# harp_analog_input_v1_0.net
KiCad netlist of a schematic drawn in EAGLE
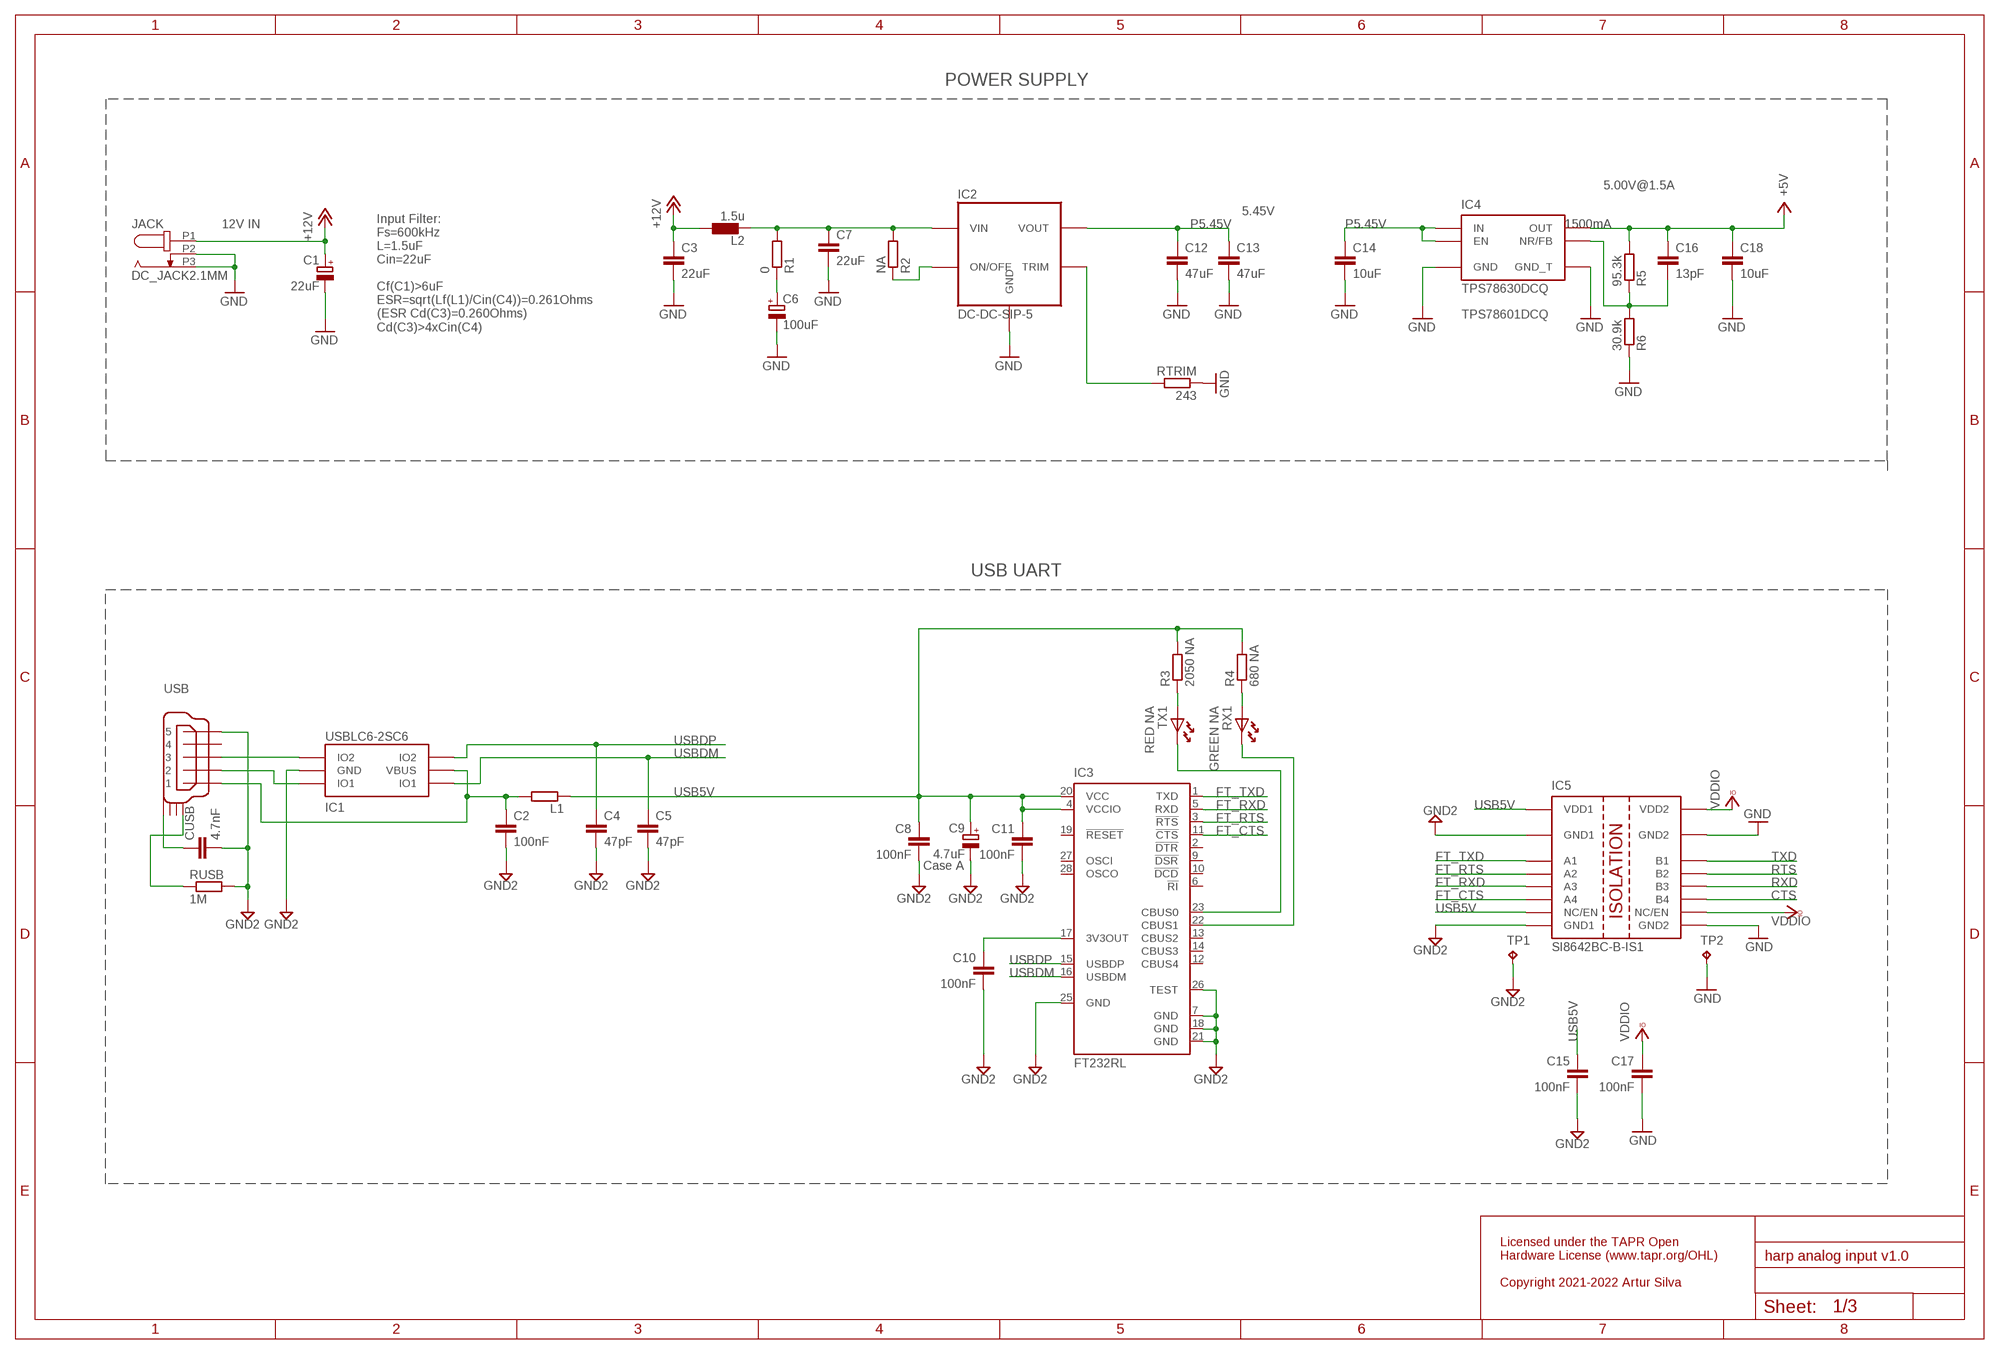
[diagram p0: schematic, sheet 1]
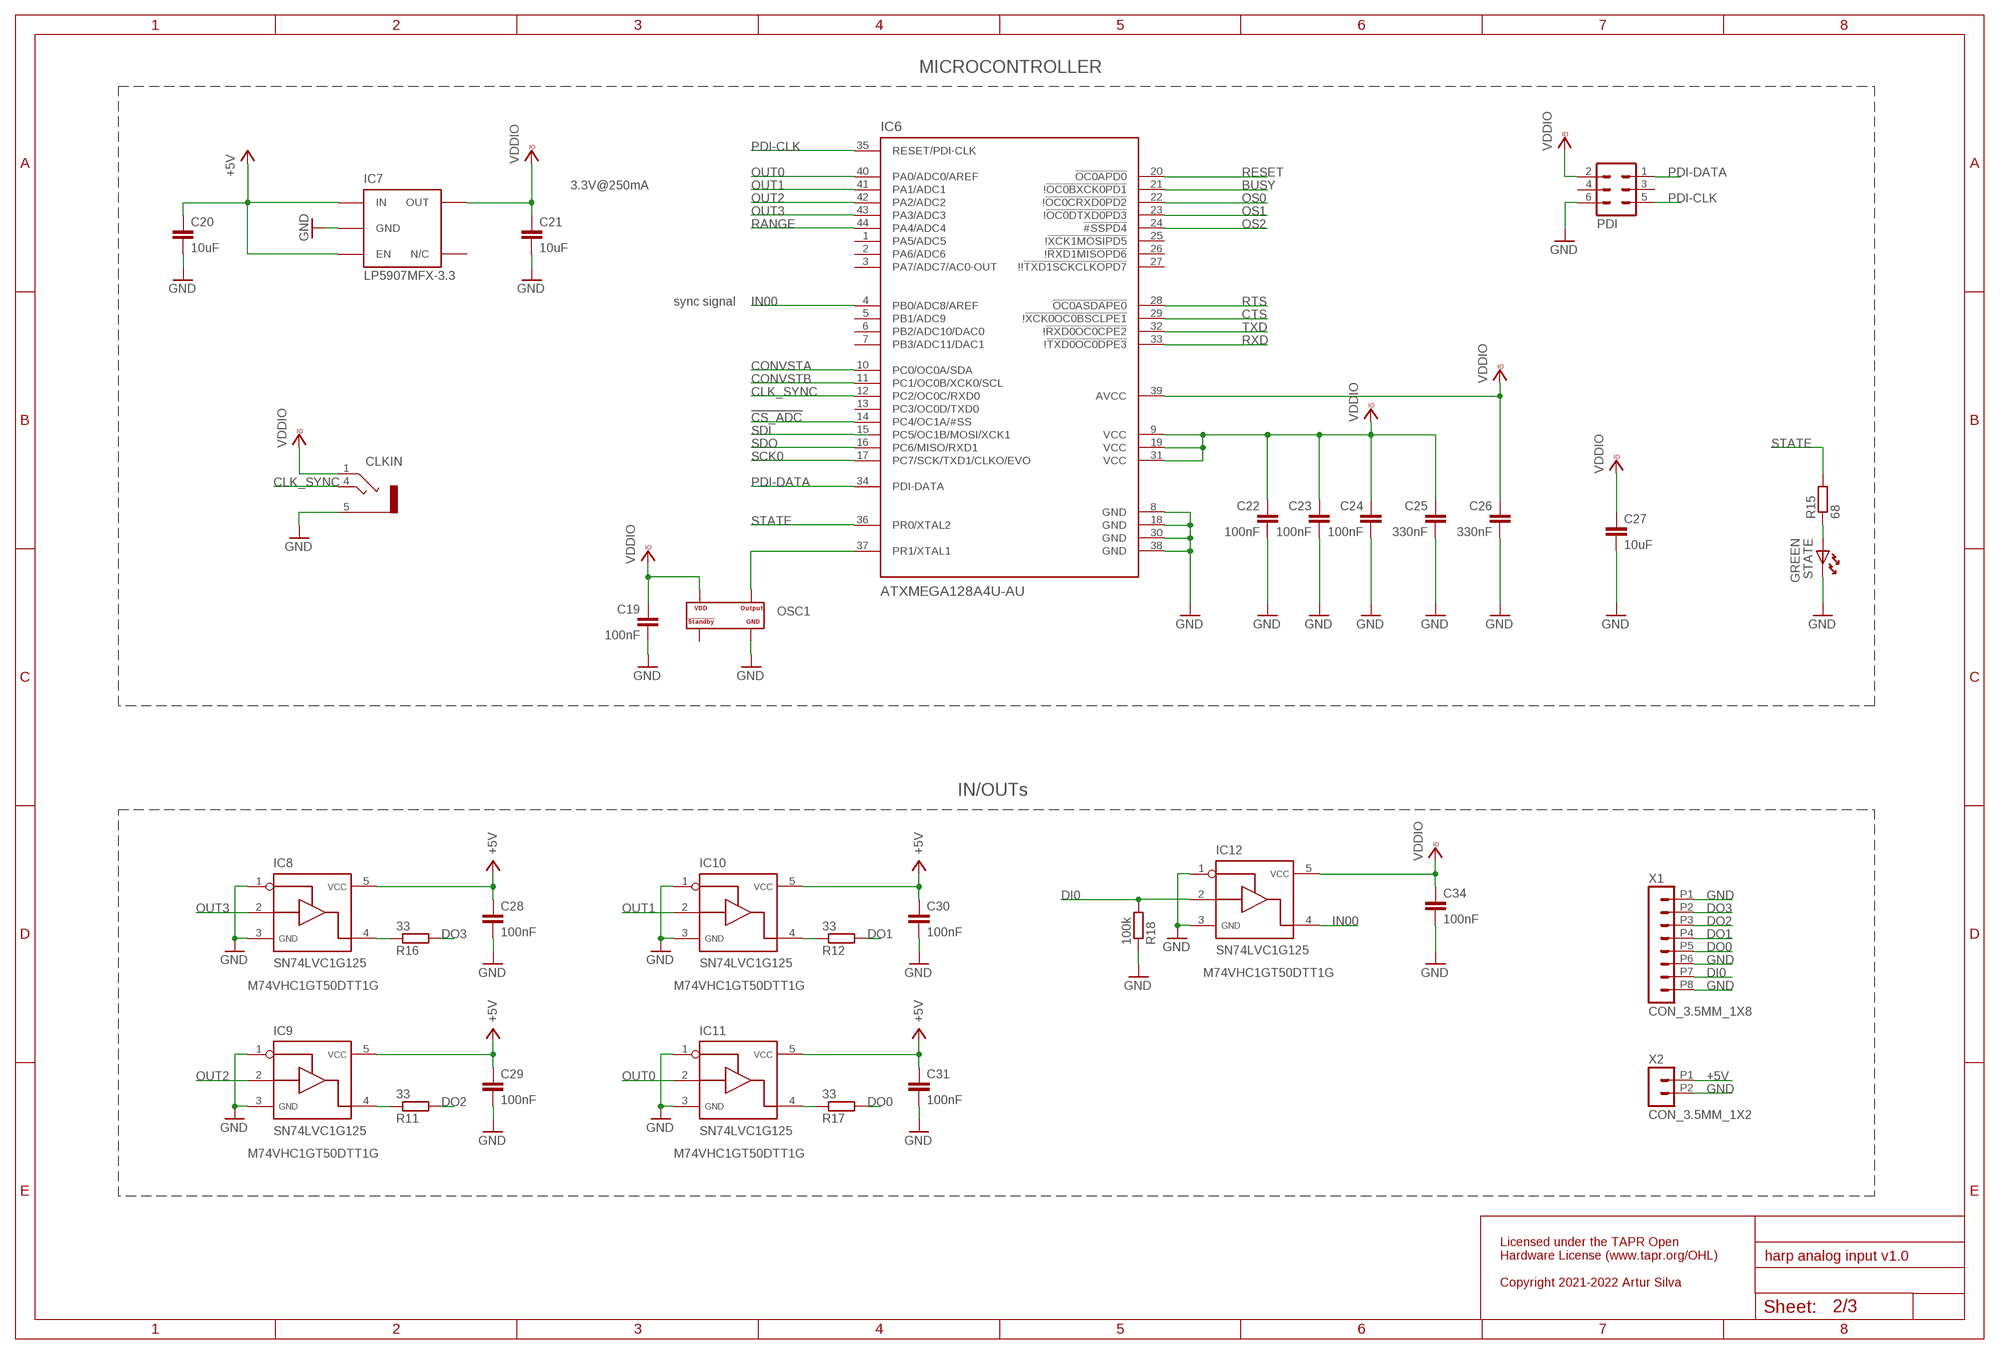
[diagram p1: schematic, sheet 2]
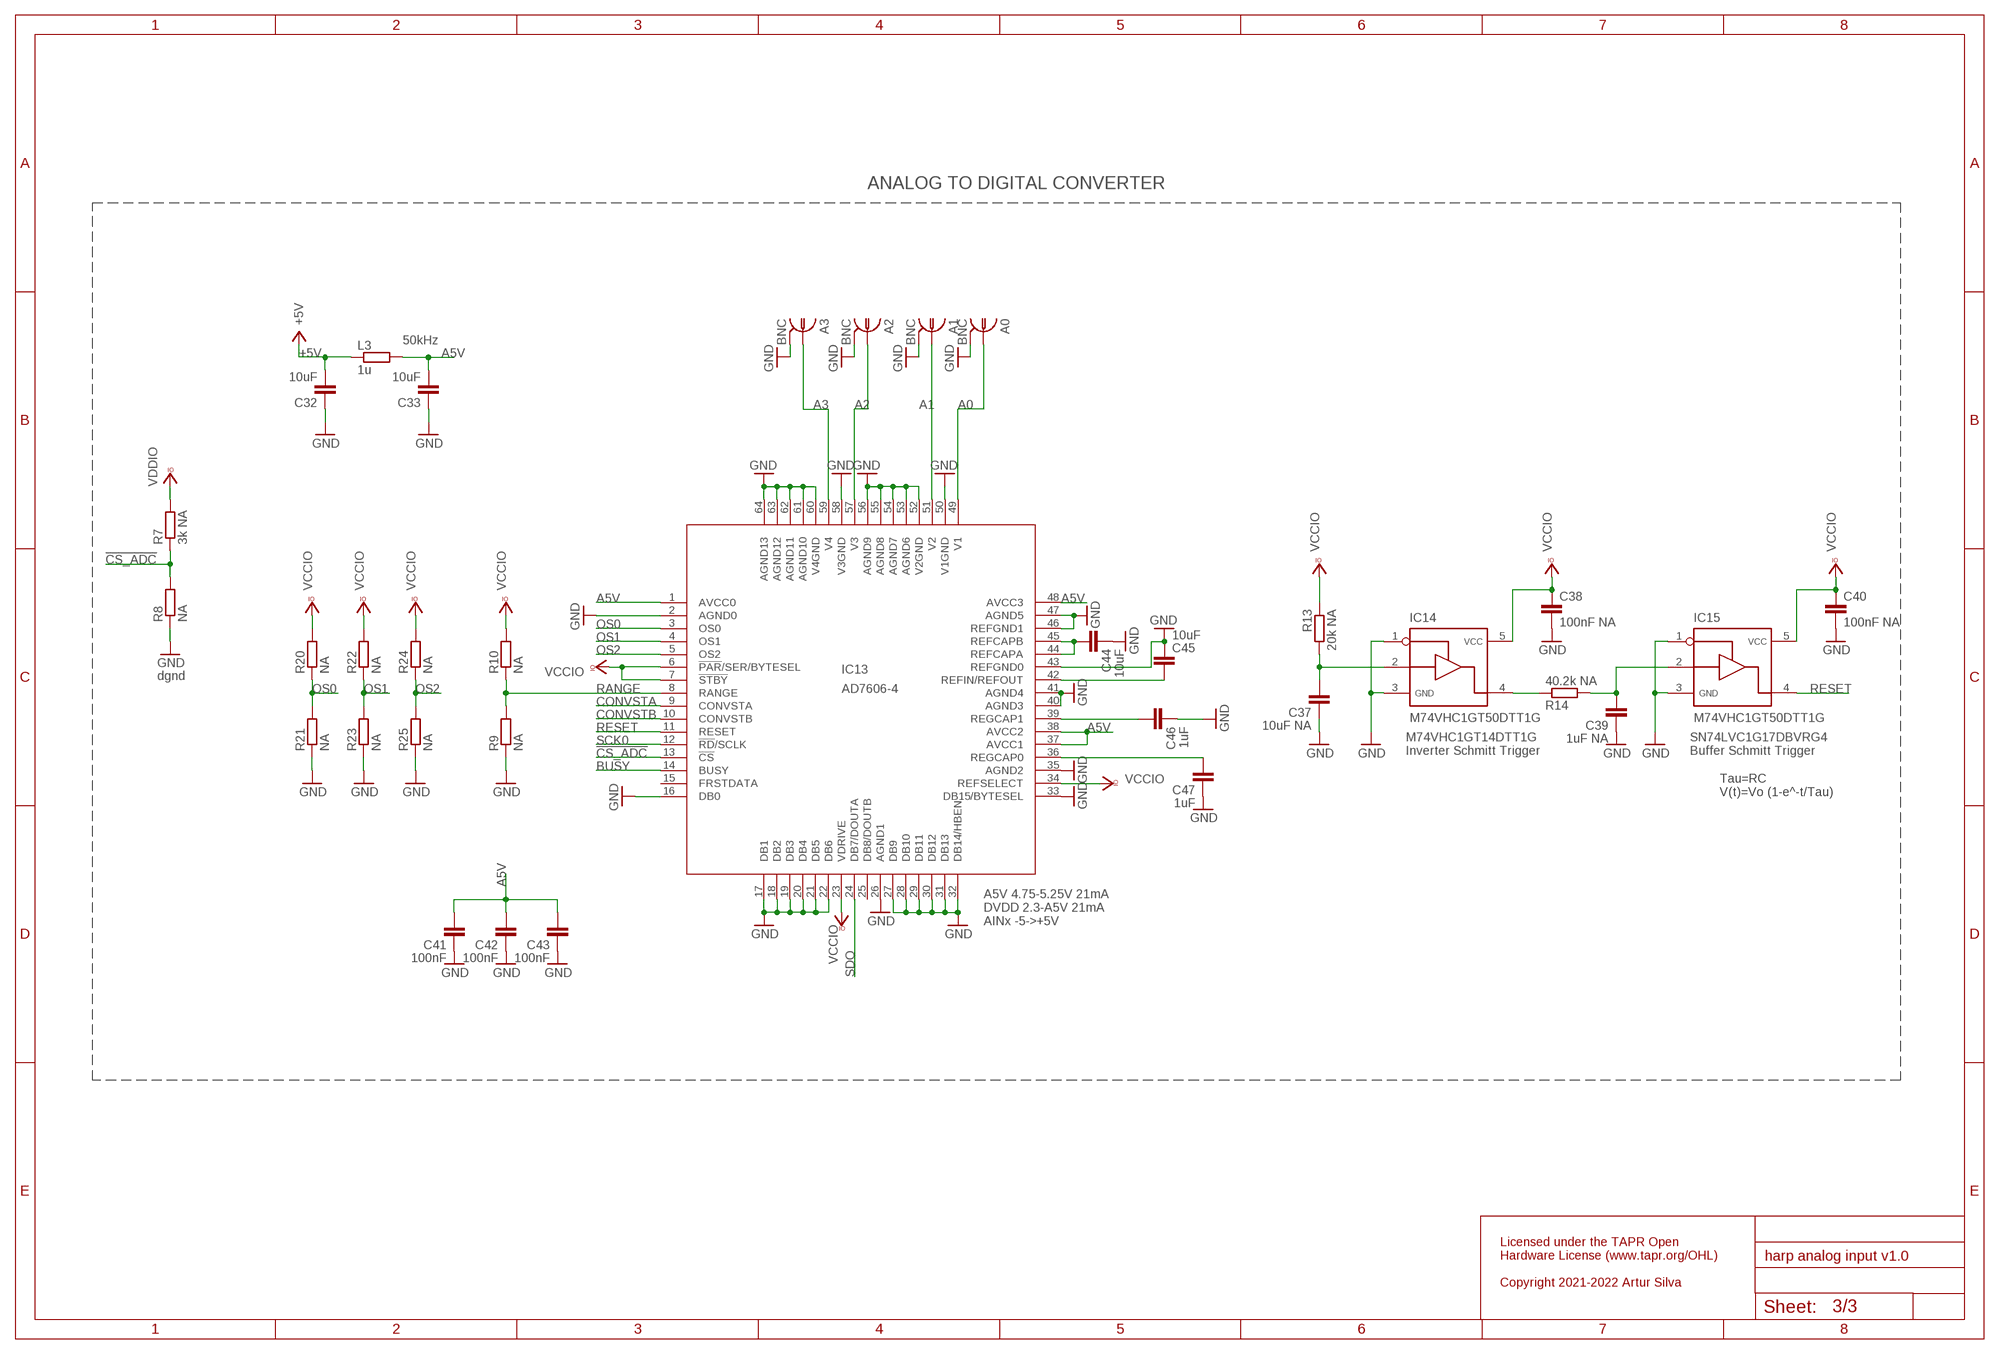
[diagram p2: schematic, sheet 3]

(export (version "E")
  (design (tool "Eeschema 10.0.6"))
  (components
    (comp (ref "C1")
      (value "22uF")
      (footprint "eagle-import:CAP_100UF_HAND")
      (libsource (lib "eagle-import") (part "CAP_100UFHAND"))
    )
    (comp (ref "C2")
      (value "100nF")
      (footprint "eagle-import:C0402")
      (libsource (lib "eagle-import") (part "C-EUC0402"))
    )
    (comp (ref "C3")
      (value "22uF")
      (footprint "eagle-import:C1210")
      (libsource (lib "eagle-import") (part "C-EUC1210"))
    )
    (comp (ref "C4")
      (value "47pF")
      (footprint "eagle-import:C0402")
      (libsource (lib "eagle-import") (part "C-EUC0402"))
    )
    (comp (ref "C5")
      (value "47pF")
      (footprint "eagle-import:C0402")
      (libsource (lib "eagle-import") (part "C-EUC0402"))
    )
    (comp (ref "C6")
      (value "100uF")
      (footprint "eagle-import:PANASONIC_E")
      (libsource (lib "eagle-import") (part "CPOL-EUE"))
    )
    (comp (ref "C7")
      (value "22uF")
      (footprint "eagle-import:C1210")
      (libsource (lib "eagle-import") (part "C-EUC1210"))
    )
    (comp (ref "C8")
      (value "100nF")
      (footprint "eagle-import:C0402")
      (libsource (lib "eagle-import") (part "C-EUC0402"))
    )
    (comp (ref "C9")
      (value "4.7uF")
      (footprint "eagle-import:A_3216-18W")
      (libsource (lib "eagle-import") (part "CPOL-EUA/3216-18W"))
    )
    (comp (ref "C10")
      (value "100nF")
      (footprint "eagle-import:C0402")
      (libsource (lib "eagle-import") (part "C-EUC0402"))
    )
    (comp (ref "C11")
      (value "100nF")
      (footprint "eagle-import:C0402")
      (libsource (lib "eagle-import") (part "C-EUC0402"))
    )
    (comp (ref "C12")
      (value "47uF")
      (footprint "eagle-import:C1210")
      (libsource (lib "eagle-import") (part "C-EUC1210"))
    )
    (comp (ref "C13")
      (value "47uF")
      (footprint "eagle-import:C1210")
      (libsource (lib "eagle-import") (part "C-EUC1210"))
    )
    (comp (ref "C14")
      (value "10uF")
      (footprint "eagle-import:C0603")
      (libsource (lib "eagle-import") (part "C-EUC0603"))
    )
    (comp (ref "C15")
      (value "100nF")
      (footprint "eagle-import:C0402")
      (libsource (lib "eagle-import") (part "C-EUC0402"))
    )
    (comp (ref "C16")
      (value "13pF")
      (footprint "eagle-import:C0402")
      (libsource (lib "eagle-import") (part "C-EUC0402"))
    )
    (comp (ref "C17")
      (value "100nF")
      (footprint "eagle-import:C0402")
      (libsource (lib "eagle-import") (part "C-EUC0402"))
    )
    (comp (ref "C18")
      (value "10uF")
      (footprint "eagle-import:C0603")
      (libsource (lib "eagle-import") (part "C-EUC0603"))
    )
    (comp (ref "CUSB")
      (value "4.7nF")
      (footprint "eagle-import:C0402")
      (libsource (lib "eagle-import") (part "C-EUC0402"))
    )
    (comp (ref "IC1")
      (value "USBLC6-2SC6")
      (footprint "eagle-import:SOT23-6L")
      (libsource (lib "eagle-import") (part "USBLC6-2"))
    )
    (comp (ref "IC2")
      (value "DC-DC-SIP-5")
      (footprint "eagle-import:SIP-5")
      (libsource (lib "eagle-import") (part "DC-DC-SIP-5"))
    )
    (comp (ref "IC3")
      (value "FT232RL")
      (footprint "eagle-import:SSOP28")
      (libsource (lib "eagle-import") (part "FT232RL"))
    )
    (comp (ref "IC4")
      (value "TPS78630DCQ")
      (footprint "eagle-import:SON-8")
      (libsource (lib "eagle-import") (part "TPS78601SON"))
    )
    (comp (ref "IC5")
      (value "SI8642BC-B-IS1")
      (footprint "eagle-import:NSOIC-16")
      (libsource (lib "eagle-import") (part "SI8645"))
    )
    (comp (ref "JACK")
      (value "DC_JACK2.1MM")
      (footprint "eagle-import:DC_POWER_INPUT_2.1MM")
      (libsource (lib "eagle-import") (part "DC_JACK2.1MM"))
    )
    (comp (ref "L1")
      (value "???")
      (footprint "eagle-import:R0805")
      (libsource (lib "eagle-import") (part "R-EU_R0805"))
    )
    (comp (ref "L2")
      (value "1.5u")
      (footprint "eagle-import:IND_LPS4012")
      (libsource (lib "eagle-import") (part "INDLPS4012"))
    )
    (comp (ref "R1")
      (value "0")
      (footprint "eagle-import:R0402")
      (libsource (lib "eagle-import") (part "R-EU_R0402"))
    )
    (comp (ref "R2")
      (value "NA")
      (footprint "eagle-import:R0402")
      (libsource (lib "eagle-import") (part "R-EU_R0402"))
    )
    (comp (ref "R3")
      (value "2050 NA")
      (footprint "eagle-import:R0402")
      (libsource (lib "eagle-import") (part "R-EU_R0402"))
    )
    (comp (ref "R4")
      (value "680 NA")
      (footprint "eagle-import:R0402")
      (libsource (lib "eagle-import") (part "R-EU_R0402"))
    )
    (comp (ref "R5")
      (value "95.3k")
      (footprint "eagle-import:R0402")
      (libsource (lib "eagle-import") (part "R-EU_R0402"))
    )
    (comp (ref "R6")
      (value "30.9k")
      (footprint "eagle-import:R0402")
      (libsource (lib "eagle-import") (part "R-EU_R0402"))
    )
    (comp (ref "RTRIM")
      (value "243")
      (footprint "eagle-import:R0402")
      (libsource (lib "eagle-import") (part "R-EU_R0402"))
    )
    (comp (ref "RUSB")
      (value "1M")
      (footprint "eagle-import:R0402")
      (libsource (lib "eagle-import") (part "R-EU_R0402"))
    )
    (comp (ref "RX1")
      (value "GREEN NA")
      (footprint "eagle-import:LED_HAND")
      (libsource (lib "eagle-import") (part "LEDHAND"))
    )
    (comp (ref "TP1")
      (value "TPTP08SQ")
      (footprint "eagle-import:TP08SQ")
      (libsource (lib "eagle-import") (part "TPTP08SQ"))
    )
    (comp (ref "TP2")
      (value "TPTP08SQ")
      (footprint "eagle-import:TP08SQ")
      (libsource (lib "eagle-import") (part "TPTP08SQ"))
    )
    (comp (ref "TX1")
      (value "RED NA")
      (footprint "eagle-import:LED_HAND")
      (libsource (lib "eagle-import") (part "LEDHAND"))
    )
    (comp (ref "USB")
      (value "USB_MINI_B")
      (footprint "eagle-import:240-0002-1")
      (libsource (lib "eagle-import") (part "USB_MINI_B"))
    )
    (comp (ref "A0")
      (value "BNC")
      (footprint "eagle-import:BNC_RA")
      (libsource (lib "eagle-import") (part "BNC"))
    )
    (comp (ref "A1")
      (value "BNC")
      (footprint "eagle-import:BNC_RA")
      (libsource (lib "eagle-import") (part "BNC"))
    )
    (comp (ref "A2")
      (value "BNC")
      (footprint "eagle-import:BNC_RA")
      (libsource (lib "eagle-import") (part "BNC"))
    )
    (comp (ref "A3")
      (value "BNC")
      (footprint "eagle-import:BNC_RA")
      (libsource (lib "eagle-import") (part "BNC"))
    )
    (comp (ref "C32")
      (value "10uF")
      (footprint "eagle-import:C0603")
      (libsource (lib "eagle-import") (part "C-EUC0603"))
    )
    (comp (ref "C33")
      (value "10uF")
      (footprint "eagle-import:C0603")
      (libsource (lib "eagle-import") (part "C-EUC0603"))
    )
    (comp (ref "C37")
      (value "10uF NA")
      (footprint "eagle-import:C0603")
      (libsource (lib "eagle-import") (part "C-EUC0603"))
    )
    (comp (ref "C38")
      (value "100nF NA")
      (footprint "eagle-import:C0402")
      (libsource (lib "eagle-import") (part "C-EUC0402"))
    )
    (comp (ref "C39")
      (value "1uF NA")
      (footprint "eagle-import:C0402")
      (libsource (lib "eagle-import") (part "C-EUC0402"))
    )
    (comp (ref "C40")
      (value "100nF NA")
      (footprint "eagle-import:C0402")
      (libsource (lib "eagle-import") (part "C-EUC0402"))
    )
    (comp (ref "C41")
      (value "100nF")
      (footprint "eagle-import:C0402")
      (libsource (lib "eagle-import") (part "C-EUC0402"))
    )
    (comp (ref "C42")
      (value "100nF")
      (footprint "eagle-import:C0402")
      (libsource (lib "eagle-import") (part "C-EUC0402"))
    )
    (comp (ref "C43")
      (value "100nF")
      (footprint "eagle-import:C0402")
      (libsource (lib "eagle-import") (part "C-EUC0402"))
    )
    (comp (ref "C44")
      (value "10uF")
      (footprint "eagle-import:C0603")
      (libsource (lib "eagle-import") (part "C-EUC0603"))
    )
    (comp (ref "C45")
      (value "10uF")
      (footprint "eagle-import:C0603")
      (libsource (lib "eagle-import") (part "C-EUC0603"))
    )
    (comp (ref "C46")
      (value "1uF")
      (footprint "eagle-import:C0402")
      (libsource (lib "eagle-import") (part "C-EUC0402"))
    )
    (comp (ref "C47")
      (value "1uF")
      (footprint "eagle-import:C0402")
      (libsource (lib "eagle-import") (part "C-EUC0402"))
    )
    (comp (ref "IC13")
      (value "AD7606-4")
      (footprint "eagle-import:LQFP-64")
      (libsource (lib "eagle-import") (part "AD7606-4"))
    )
    (comp (ref "IC14")
      (value "M74VHC1GT50DTT1G")
      (footprint "eagle-import:SOT23-5")
      (libsource (lib "eagle-import") (part "SN74LVC1G125"))
    )
    (comp (ref "IC15")
      (value "M74VHC1GT50DTT1G")
      (footprint "eagle-import:SOT23-5")
      (libsource (lib "eagle-import") (part "SN74LVC1G125"))
    )
    (comp (ref "L3")
      (value "1u")
      (footprint "eagle-import:R0402")
      (libsource (lib "eagle-import") (part "R-EU_R0402"))
    )
    (comp (ref "R7")
      (value "3k NA")
      (footprint "eagle-import:R0402")
      (libsource (lib "eagle-import") (part "R-EU_R0402"))
    )
    (comp (ref "R8")
      (value "NA")
      (footprint "eagle-import:R0402")
      (libsource (lib "eagle-import") (part "R-EU_R0402"))
    )
    (comp (ref "R9")
      (value "NA")
      (footprint "eagle-import:R0402")
      (libsource (lib "eagle-import") (part "R-EU_R0402"))
    )
    (comp (ref "R10")
      (value "NA")
      (footprint "eagle-import:R0402")
      (libsource (lib "eagle-import") (part "R-EU_R0402"))
    )
    (comp (ref "R13")
      (value "20k NA")
      (footprint "eagle-import:R0402")
      (libsource (lib "eagle-import") (part "R-EU_R0402"))
    )
    (comp (ref "R14")
      (value "40.2k NA")
      (footprint "eagle-import:R0402")
      (libsource (lib "eagle-import") (part "R-EU_R0402"))
    )
    (comp (ref "R20")
      (value "NA")
      (footprint "eagle-import:R0402")
      (libsource (lib "eagle-import") (part "R-EU_R0402"))
    )
    (comp (ref "R21")
      (value "NA")
      (footprint "eagle-import:R0402")
      (libsource (lib "eagle-import") (part "R-EU_R0402"))
    )
    (comp (ref "R22")
      (value "NA")
      (footprint "eagle-import:R0402")
      (libsource (lib "eagle-import") (part "R-EU_R0402"))
    )
    (comp (ref "R23")
      (value "NA")
      (footprint "eagle-import:R0402")
      (libsource (lib "eagle-import") (part "R-EU_R0402"))
    )
    (comp (ref "R24")
      (value "NA")
      (footprint "eagle-import:R0402")
      (libsource (lib "eagle-import") (part "R-EU_R0402"))
    )
    (comp (ref "R25")
      (value "NA")
      (footprint "eagle-import:R0402")
      (libsource (lib "eagle-import") (part "R-EU_R0402"))
    )
    (comp (ref "C19")
      (value "100nF")
      (footprint "eagle-import:C0402")
      (libsource (lib "eagle-import") (part "C-EUC0402"))
    )
    (comp (ref "C20")
      (value "10uF")
      (footprint "eagle-import:C0603")
      (libsource (lib "eagle-import") (part "C-EUC0603"))
    )
    (comp (ref "C21")
      (value "10uF")
      (footprint "eagle-import:C0603")
      (libsource (lib "eagle-import") (part "C-EUC0603"))
    )
    (comp (ref "C22")
      (value "100nF")
      (footprint "eagle-import:C0402")
      (libsource (lib "eagle-import") (part "C-EUC0402"))
    )
    (comp (ref "C23")
      (value "100nF")
      (footprint "eagle-import:C0402")
      (libsource (lib "eagle-import") (part "C-EUC0402"))
    )
    (comp (ref "C24")
      (value "100nF")
      (footprint "eagle-import:C0402")
      (libsource (lib "eagle-import") (part "C-EUC0402"))
    )
    (comp (ref "C25")
      (value "330nF")
      (footprint "eagle-import:C0402")
      (libsource (lib "eagle-import") (part "C-EUC0402"))
    )
    (comp (ref "C26")
      (value "330nF")
      (footprint "eagle-import:C0402")
      (libsource (lib "eagle-import") (part "C-EUC0402"))
    )
    (comp (ref "C27")
      (value "10uF")
      (footprint "eagle-import:C0603")
      (libsource (lib "eagle-import") (part "C-EUC0603"))
    )
    (comp (ref "C28")
      (value "100nF")
      (footprint "eagle-import:C0402")
      (libsource (lib "eagle-import") (part "C-EUC0402"))
    )
    (comp (ref "C29")
      (value "100nF")
      (footprint "eagle-import:C0402")
      (libsource (lib "eagle-import") (part "C-EUC0402"))
    )
    (comp (ref "C30")
      (value "100nF")
      (footprint "eagle-import:C0402")
      (libsource (lib "eagle-import") (part "C-EUC0402"))
    )
    (comp (ref "C31")
      (value "100nF")
      (footprint "eagle-import:C0402")
      (libsource (lib "eagle-import") (part "C-EUC0402"))
    )
    (comp (ref "C34")
      (value "100nF")
      (footprint "eagle-import:C0402")
      (libsource (lib "eagle-import") (part "C-EUC0402"))
    )
    (comp (ref "CLKIN")
      (value "STEREO_JACK")
      (footprint "eagle-import:35RASMT2BHNTRX")
      (libsource (lib "eagle-import") (part "STEREO_JACK"))
    )
    (comp (ref "IC6")
      (value "ATXMEGA128A4U-AU")
      (footprint "eagle-import:QFP80P1200X1200X120-44N")
      (libsource (lib "eagle-import") (part "AT-XMEGA-XXA4-AU"))
    )
    (comp (ref "IC7")
      (value "LP5907MFX-3.3")
      (footprint "eagle-import:TSOT23-5")
      (libsource (lib "eagle-import") (part "TLV700XX"))
    )
    (comp (ref "IC8")
      (value "SN74LVC1G125")
      (footprint "eagle-import:SOT23-5")
      (libsource (lib "eagle-import") (part "SN74LVC1G125"))
    )
    (comp (ref "IC9")
      (value "SN74LVC1G125")
      (footprint "eagle-import:SOT23-5")
      (libsource (lib "eagle-import") (part "SN74LVC1G125"))
    )
    (comp (ref "IC10")
      (value "SN74LVC1G125")
      (footprint "eagle-import:SOT23-5")
      (libsource (lib "eagle-import") (part "SN74LVC1G125"))
    )
    (comp (ref "IC11")
      (value "SN74LVC1G125")
      (footprint "eagle-import:SOT23-5")
      (libsource (lib "eagle-import") (part "SN74LVC1G125"))
    )
    (comp (ref "IC12")
      (value "SN74LVC1G125")
      (footprint "eagle-import:SOT23-5")
      (libsource (lib "eagle-import") (part "SN74LVC1G125"))
    )
    (comp (ref "OSC1")
      (value "OSCILLATOR")
      (footprint "eagle-import:OSCILLATOR_3.2X2.5")
      (libsource (lib "eagle-import") (part "OSCILLATOR"))
    )
    (comp (ref "PDI")
      (value "MA03-2")
      (footprint "eagle-import:MA03-2")
      (libsource (lib "eagle-import") (part "MA03-2"))
    )
    (comp (ref "R11")
      (value "33")
      (footprint "eagle-import:R0402")
      (libsource (lib "eagle-import") (part "R-EU_R0402"))
    )
    (comp (ref "R12")
      (value "33")
      (footprint "eagle-import:R0402")
      (libsource (lib "eagle-import") (part "R-EU_R0402"))
    )
    (comp (ref "R15")
      (value "68")
      (footprint "eagle-import:R0402")
      (libsource (lib "eagle-import") (part "R-EU_R0402"))
    )
    (comp (ref "R16")
      (value "33")
      (footprint "eagle-import:R0402")
      (libsource (lib "eagle-import") (part "R-EU_R0402"))
    )
    (comp (ref "R17")
      (value "33")
      (footprint "eagle-import:R0402")
      (libsource (lib "eagle-import") (part "R-EU_R0402"))
    )
    (comp (ref "R18")
      (value "100k")
      (footprint "eagle-import:R0402")
      (libsource (lib "eagle-import") (part "R-EU_R0402"))
    )
    (comp (ref "STATE")
      (value "GREEN")
      (footprint "eagle-import:LED_HAND")
      (libsource (lib "eagle-import") (part "LEDHAND"))
    )
    (comp (ref "X1")
      (value "CON_3.5MM_1X8")
      (footprint "eagle-import:CON_3.5MM_1X8")
      (libsource (lib "eagle-import") (part "CON_3.5MM_1X8"))
    )
    (comp (ref "X2")
      (value "CON_3.5MM_1X2")
      (footprint "eagle-import:CON_3.5MM_1X2")
      (libsource (lib "eagle-import") (part "CON_3.5MM_1X2"))
    )
  )
  (nets
    (net (code "1") (name "+5V") (class "Default")
      (node (ref "C16") (pin "1") (pinfunction "1_1") (pintype "passive"))
      (node (ref "C18") (pin "1") (pinfunction "1_1") (pintype "passive"))
      (node (ref "C20") (pin "1") (pinfunction "1_1") (pintype "passive"))
      (node (ref "C28") (pin "1") (pinfunction "1_1") (pintype "passive"))
      (node (ref "C29") (pin "1") (pinfunction "1_1") (pintype "passive"))
      (node (ref "C30") (pin "1") (pinfunction "1_1") (pintype "passive"))
      (node (ref "C31") (pin "1") (pinfunction "1_1") (pintype "passive"))
      (node (ref "C32") (pin "2") (pinfunction "2_2") (pintype "passive"))
      (node (ref "IC10") (pin "5") (pinfunction "P$5_5") (pintype "bidirectional"))
      (node (ref "IC11") (pin "5") (pinfunction "P$5_5") (pintype "bidirectional"))
      (node (ref "IC4") (pin "P3") (pinfunction "OUT_P3") (pintype "bidirectional"))
      (node (ref "IC4") (pin "P4") (pinfunction "OUT_P4") (pintype "bidirectional"))
      (node (ref "IC7") (pin "1") (pinfunction "IN_1") (pintype "bidirectional"))
      (node (ref "IC7") (pin "3") (pinfunction "EN_3") (pintype "bidirectional"))
      (node (ref "IC8") (pin "5") (pinfunction "P$5_5") (pintype "bidirectional"))
      (node (ref "IC9") (pin "5") (pinfunction "P$5_5") (pintype "bidirectional"))
      (node (ref "L3") (pin "1") (pinfunction "1_1") (pintype "passive"))
      (node (ref "R5") (pin "2") (pinfunction "2_2") (pintype "passive"))
      (node (ref "X2") (pin "P1") (pinfunction "1_P1") (pintype "passive"))
    )
    (net (code "2") (name "+12V") (class "Default")
      (node (ref "C1") (pin "+") (pinfunction "+_+") (pintype "passive"))
      (node (ref "C3") (pin "1") (pinfunction "1_1") (pintype "passive"))
      (node (ref "JACK") (pin "P1") (pinfunction "1_P1") (pintype "passive"))
      (node (ref "L2") (pin "1") (pinfunction "1_1") (pintype "passive"))
    )
    (net (code "3") (name "A0") (class "Default")
      (node (ref "A0") (pin "1") (pinfunction "1_1") (pintype "passive"))
      (node (ref "IC13") (pin "49") (pinfunction "V1_49") (pintype "bidirectional"))
    )
    (net (code "4") (name "A1") (class "Default")
      (node (ref "A1") (pin "1") (pinfunction "1_1") (pintype "passive"))
      (node (ref "IC13") (pin "51") (pinfunction "V2_51") (pintype "bidirectional"))
    )
    (net (code "5") (name "A2") (class "Default")
      (node (ref "A2") (pin "1") (pinfunction "1_1") (pintype "passive"))
      (node (ref "IC13") (pin "57") (pinfunction "V3_57") (pintype "bidirectional"))
    )
    (net (code "6") (name "A3") (class "Default")
      (node (ref "A3") (pin "1") (pinfunction "1_1") (pintype "passive"))
      (node (ref "IC13") (pin "59") (pinfunction "V4_59") (pintype "bidirectional"))
    )
    (net (code "7") (name "A5V") (class "Default")
      (node (ref "C33") (pin "2") (pinfunction "2_2") (pintype "passive"))
      (node (ref "C41") (pin "2") (pinfunction "2_2") (pintype "passive"))
      (node (ref "C42") (pin "2") (pinfunction "2_2") (pintype "passive"))
      (node (ref "C43") (pin "2") (pinfunction "2_2") (pintype "passive"))
      (node (ref "IC13") (pin "1") (pinfunction "AVCC0_1") (pintype "bidirectional"))
      (node (ref "IC13") (pin "37") (pinfunction "AVCC1_37") (pintype "bidirectional"))
      (node (ref "IC13") (pin "38") (pinfunction "AVCC2_38") (pintype "bidirectional"))
      (node (ref "IC13") (pin "48") (pinfunction "AVCC3_48") (pintype "bidirectional"))
      (node (ref "L3") (pin "2") (pinfunction "2_2") (pintype "passive"))
    )
    (net (code "8") (name "BUSY") (class "Default")
      (node (ref "IC13") (pin "14") (pinfunction "BUSY_14") (pintype "bidirectional"))
      (node (ref "IC6") (pin "21") (pinfunction "~OC0BXCK0PD1_21") (pintype "bidirectional"))
    )
    (net (code "9") (name "CLK_SYNC") (class "Default")
      (node (ref "CLKIN") (pin "4") (pinfunction "4_4") (pintype "passive"))
      (node (ref "IC6") (pin "12") (pinfunction "PC2/OC0C/RXD0_12") (pintype "bidirectional"))
    )
    (net (code "10") (name "CONVSTA") (class "Default")
      (node (ref "IC13") (pin "9") (pinfunction "CONVSTA_9") (pintype "bidirectional"))
      (node (ref "IC6") (pin "10") (pinfunction "PC0/OC0A/SDA_10") (pintype "bidirectional"))
    )
    (net (code "11") (name "CONVSTB") (class "Default")
      (node (ref "IC13") (pin "10") (pinfunction "CONVSTB_10") (pintype "bidirectional"))
      (node (ref "IC6") (pin "11") (pinfunction "PC1/OC0B/XCK0/SCL_11") (pintype "bidirectional"))
    )
    (net (code "12") (name "CTS") (class "Default")
      (node (ref "IC5") (pin "11") (pinfunction "B4_11") (pintype "bidirectional"))
      (node (ref "IC6") (pin "29") (pinfunction "~XCK0OC0BSCLPE1_29") (pintype "bidirectional"))
    )
    (net (code "13") (name "DI0") (class "Default")
      (node (ref "IC12") (pin "2") (pinfunction "P$2_2") (pintype "bidirectional"))
      (node (ref "R18") (pin "2") (pinfunction "2_2") (pintype "passive"))
      (node (ref "X1") (pin "P7") (pinfunction "7_P7") (pintype "passive"))
    )
    (net (code "14") (name "DO0") (class "Default")
      (node (ref "R17") (pin "2") (pinfunction "2_2") (pintype "passive"))
      (node (ref "X1") (pin "P5") (pinfunction "5_P5") (pintype "passive"))
    )
    (net (code "15") (name "DO1") (class "Default")
      (node (ref "R12") (pin "2") (pinfunction "2_2") (pintype "passive"))
      (node (ref "X1") (pin "P4") (pinfunction "4_P4") (pintype "passive"))
    )
    (net (code "16") (name "DO2") (class "Default")
      (node (ref "R11") (pin "2") (pinfunction "2_2") (pintype "passive"))
      (node (ref "X1") (pin "P3") (pinfunction "3_P3") (pintype "passive"))
    )
    (net (code "17") (name "DO3") (class "Default")
      (node (ref "R16") (pin "2") (pinfunction "2_2") (pintype "passive"))
      (node (ref "X1") (pin "P2") (pinfunction "2_P2") (pintype "passive"))
    )
    (net (code "18") (name "FT_CTS") (class "Default")
      (node (ref "IC3") (pin "11") (pinfunction "~{CTS}_11") (pintype "input"))
      (node (ref "IC5") (pin "6") (pinfunction "A4_6") (pintype "bidirectional"))
    )
    (net (code "19") (name "FT_RTS") (class "Default")
      (node (ref "IC3") (pin "3") (pinfunction "~{RTS}_3") (pintype "output"))
      (node (ref "IC5") (pin "4") (pinfunction "A2_4") (pintype "bidirectional"))
    )
    (net (code "20") (name "FT_RXD") (class "Default")
      (node (ref "IC3") (pin "5") (pinfunction "RXD_5") (pintype "input"))
      (node (ref "IC5") (pin "5") (pinfunction "A3_5") (pintype "bidirectional"))
    )
    (net (code "21") (name "FT_TXD") (class "Default")
      (node (ref "IC3") (pin "1") (pinfunction "TXD_1") (pintype "output"))
      (node (ref "IC5") (pin "3") (pinfunction "A1_3") (pintype "bidirectional"))
    )
    (net (code "22") (name "GND") (class "Default")
      (node (ref "A0") (pin "2") (pinfunction "2_2") (pintype "passive"))
      (node (ref "A1") (pin "2") (pinfunction "2_2") (pintype "passive"))
      (node (ref "A2") (pin "2") (pinfunction "2_2") (pintype "passive"))
      (node (ref "A3") (pin "2") (pinfunction "2_2") (pintype "passive"))
      (node (ref "C1") (pin "-") (pinfunction "-_-") (pintype "passive"))
      (node (ref "C12") (pin "2") (pinfunction "2_2") (pintype "passive"))
      (node (ref "C13") (pin "2") (pinfunction "2_2") (pintype "passive"))
      (node (ref "C14") (pin "2") (pinfunction "2_2") (pintype "passive"))
      (node (ref "C17") (pin "2") (pinfunction "2_2") (pintype "passive"))
      (node (ref "C18") (pin "2") (pinfunction "2_2") (pintype "passive"))
      (node (ref "C19") (pin "2") (pinfunction "2_2") (pintype "passive"))
      (node (ref "C20") (pin "2") (pinfunction "2_2") (pintype "passive"))
      (node (ref "C21") (pin "2") (pinfunction "2_2") (pintype "passive"))
      (node (ref "C22") (pin "2") (pinfunction "2_2") (pintype "passive"))
      (node (ref "C23") (pin "2") (pinfunction "2_2") (pintype "passive"))
      (node (ref "C24") (pin "2") (pinfunction "2_2") (pintype "passive"))
      (node (ref "C25") (pin "2") (pinfunction "2_2") (pintype "passive"))
      (node (ref "C26") (pin "2") (pinfunction "2_2") (pintype "passive"))
      (node (ref "C27") (pin "2") (pinfunction "2_2") (pintype "passive"))
      (node (ref "C28") (pin "2") (pinfunction "2_2") (pintype "passive"))
      (node (ref "C29") (pin "2") (pinfunction "2_2") (pintype "passive"))
      (node (ref "C3") (pin "2") (pinfunction "2_2") (pintype "passive"))
      (node (ref "C30") (pin "2") (pinfunction "2_2") (pintype "passive"))
      (node (ref "C31") (pin "2") (pinfunction "2_2") (pintype "passive"))
      (node (ref "C32") (pin "1") (pinfunction "1_1") (pintype "passive"))
      (node (ref "C33") (pin "1") (pinfunction "1_1") (pintype "passive"))
      (node (ref "C34") (pin "2") (pinfunction "2_2") (pintype "passive"))
      (node (ref "C37") (pin "1") (pinfunction "1_1") (pintype "passive"))
      (node (ref "C38") (pin "2") (pinfunction "2_2") (pintype "passive"))
      (node (ref "C39") (pin "1") (pinfunction "1_1") (pintype "passive"))
      (node (ref "C40") (pin "2") (pinfunction "2_2") (pintype "passive"))
      (node (ref "C41") (pin "1") (pinfunction "1_1") (pintype "passive"))
      (node (ref "C42") (pin "1") (pinfunction "1_1") (pintype "passive"))
      (node (ref "C43") (pin "1") (pinfunction "1_1") (pintype "passive"))
      (node (ref "C44") (pin "1") (pinfunction "1_1") (pintype "passive"))
      (node (ref "C45") (pin "1") (pinfunction "1_1") (pintype "passive"))
      (node (ref "C46") (pin "1") (pinfunction "1_1") (pintype "passive"))
      (node (ref "C47") (pin "1") (pinfunction "1_1") (pintype "passive"))
      (node (ref "C6") (pin "-") (pinfunction "-_-") (pintype "passive"))
      (node (ref "C7") (pin "2") (pinfunction "2_2") (pintype "passive"))
      (node (ref "CLKIN") (pin "5") (pinfunction "5_5") (pintype "passive"))
      (node (ref "IC10") (pin "1") (pinfunction "P$1_1") (pintype "bidirectional"))
      (node (ref "IC10") (pin "3") (pinfunction "P$3_3") (pintype "bidirectional"))
      (node (ref "IC11") (pin "1") (pinfunction "P$1_1") (pintype "bidirectional"))
      (node (ref "IC11") (pin "3") (pinfunction "P$3_3") (pintype "bidirectional"))
      (node (ref "IC12") (pin "1") (pinfunction "P$1_1") (pintype "bidirectional"))
      (node (ref "IC12") (pin "3") (pinfunction "P$3_3") (pintype "bidirectional"))
      (node (ref "IC13") (pin "16") (pinfunction "DB0_16") (pintype "bidirectional"))
      (node (ref "IC13") (pin "17") (pinfunction "DB1_17") (pintype "bidirectional"))
      (node (ref "IC13") (pin "18") (pinfunction "DB2_18") (pintype "bidirectional"))
      (node (ref "IC13") (pin "19") (pinfunction "DB3_19") (pintype "bidirectional"))
      (node (ref "IC13") (pin "2") (pinfunction "AGND0_2") (pintype "bidirectional"))
      (node (ref "IC13") (pin "20") (pinfunction "DB4_20") (pintype "bidirectional"))
      (node (ref "IC13") (pin "21") (pinfunction "DB5_21") (pintype "bidirectional"))
      (node (ref "IC13") (pin "22") (pinfunction "DB6_22") (pintype "bidirectional"))
      (node (ref "IC13") (pin "26") (pinfunction "AGND1_26") (pintype "bidirectional"))
      (node (ref "IC13") (pin "27") (pinfunction "DB9_27") (pintype "bidirectional"))
      (node (ref "IC13") (pin "28") (pinfunction "DB10_28") (pintype "bidirectional"))
      (node (ref "IC13") (pin "29") (pinfunction "DB11_29") (pintype "input"))
      (node (ref "IC13") (pin "30") (pinfunction "DB12_30") (pintype "bidirectional"))
      (node (ref "IC13") (pin "31") (pinfunction "DB13_31") (pintype "bidirectional"))
      (node (ref "IC13") (pin "32") (pinfunction "DB14/HBEN_32") (pintype "bidirectional"))
      (node (ref "IC13") (pin "33") (pinfunction "DB15/BYTESEL_33") (pintype "bidirectional"))
      (node (ref "IC13") (pin "35") (pinfunction "AGND2_35") (pintype "bidirectional"))
      (node (ref "IC13") (pin "40") (pinfunction "AGND3_40") (pintype "bidirectional"))
      (node (ref "IC13") (pin "41") (pinfunction "AGND4_41") (pintype "bidirectional"))
      (node (ref "IC13") (pin "43") (pinfunction "REFGND0_43") (pintype "bidirectional"))
      (node (ref "IC13") (pin "46") (pinfunction "REFGND1_46") (pintype "bidirectional"))
      (node (ref "IC13") (pin "47") (pinfunction "AGND5_47") (pintype "bidirectional"))
      (node (ref "IC13") (pin "50") (pinfunction "V1GND_50") (pintype "bidirectional"))
      (node (ref "IC13") (pin "52") (pinfunction "V2GND_52") (pintype "bidirectional"))
      (node (ref "IC13") (pin "53") (pinfunction "AGND6_53") (pintype "bidirectional"))
      (node (ref "IC13") (pin "54") (pinfunction "AGND7_54") (pintype "bidirectional"))
      (node (ref "IC13") (pin "55") (pinfunction "AGND8_55") (pintype "bidirectional"))
      (node (ref "IC13") (pin "56") (pinfunction "AGND9_56") (pintype "bidirectional"))
      (node (ref "IC13") (pin "58") (pinfunction "V3GND_58") (pintype "bidirectional"))
      (node (ref "IC13") (pin "60") (pinfunction "V4GND_60") (pintype "bidirectional"))
      (node (ref "IC13") (pin "61") (pinfunction "AGND10_61") (pintype "bidirectional"))
      (node (ref "IC13") (pin "62") (pinfunction "AGND11_62") (pintype "bidirectional"))
      (node (ref "IC13") (pin "63") (pinfunction "AGND12_63") (pintype "bidirectional"))
      (node (ref "IC13") (pin "64") (pinfunction "AGND13_64") (pintype "bidirectional"))
      (node (ref "IC14") (pin "1") (pinfunction "P$1_1") (pintype "bidirectional"))
      (node (ref "IC14") (pin "3") (pinfunction "P$3_3") (pintype "bidirectional"))
      (node (ref "IC15") (pin "1") (pinfunction "P$1_1") (pintype "bidirectional"))
      (node (ref "IC15") (pin "3") (pinfunction "P$3_3") (pintype "bidirectional"))
      (node (ref "IC2") (pin "P3") (pinfunction "GND_P3") (pintype "passive"))
      (node (ref "IC4") (pin "P6") (pinfunction "GND_P6") (pintype "bidirectional"))
      (node (ref "IC4") (pin "P9") (pinfunction "GND_T_P9") (pintype "bidirectional"))
      (node (ref "IC5") (pin "15") (pinfunction "GND2_15") (pintype "bidirectional"))
      (node (ref "IC5") (pin "9") (pinfunction "GND2_9") (pintype "bidirectional"))
      (node (ref "IC6") (pin "18") (pinfunction "GND_18") (pintype "power_in"))
      (node (ref "IC6") (pin "30") (pinfunction "GND_30") (pintype "power_in"))
      (node (ref "IC6") (pin "38") (pinfunction "GND_38") (pintype "power_in"))
      (node (ref "IC6") (pin "8") (pinfunction "GND_8") (pintype "power_in"))
      (node (ref "IC7") (pin "2") (pinfunction "GND_2") (pintype "bidirectional"))
      (node (ref "IC8") (pin "1") (pinfunction "P$1_1") (pintype "bidirectional"))
      (node (ref "IC8") (pin "3") (pinfunction "P$3_3") (pintype "bidirectional"))
      (node (ref "IC9") (pin "1") (pinfunction "P$1_1") (pintype "bidirectional"))
      (node (ref "IC9") (pin "3") (pinfunction "P$3_3") (pintype "bidirectional"))
      (node (ref "JACK") (pin "P2") (pinfunction "2_P2") (pintype "passive"))
      (node (ref "JACK") (pin "P3") (pinfunction "3_P3") (pintype "passive"))
      (node (ref "OSC1") (pin "P$2") (pinfunction "GND_P$2") (pintype "passive"))
      (node (ref "PDI") (pin "6") (pinfunction "6_6") (pintype "passive"))
      (node (ref "R18") (pin "1") (pinfunction "1_1") (pintype "passive"))
      (node (ref "R21") (pin "1") (pinfunction "1_1") (pintype "passive"))
      (node (ref "R23") (pin "1") (pinfunction "1_1") (pintype "passive"))
      (node (ref "R25") (pin "1") (pinfunction "1_1") (pintype "passive"))
      (node (ref "R6") (pin "1") (pinfunction "1_1") (pintype "passive"))
      (node (ref "R8") (pin "1") (pinfunction "1_1") (pintype "passive"))
      (node (ref "R9") (pin "1") (pinfunction "1_1") (pintype "passive"))
      (node (ref "RTRIM") (pin "1") (pinfunction "1_1") (pintype "passive"))
      (node (ref "STATE") (pin "K") (pinfunction "K_K") (pintype "bidirectional"))
      (node (ref "TP2") (pin "TP") (pinfunction "TP_TP") (pintype "input"))
      (node (ref "X1") (pin "P1") (pinfunction "1_P1") (pintype "passive"))
      (node (ref "X1") (pin "P6") (pinfunction "6_P6") (pintype "passive"))
      (node (ref "X1") (pin "P8") (pinfunction "8_P8") (pintype "passive"))
      (node (ref "X2") (pin "P2") (pinfunction "2_P2") (pintype "passive"))
    )
    (net (code "23") (name "GND2") (class "Default")
      (node (ref "C10") (pin "2") (pinfunction "2_2") (pintype "passive"))
      (node (ref "C11") (pin "2") (pinfunction "2_2") (pintype "passive"))
      (node (ref "C15") (pin "2") (pinfunction "2_2") (pintype "passive"))
      (node (ref "C2") (pin "2") (pinfunction "2_2") (pintype "passive"))
      (node (ref "C4") (pin "2") (pinfunction "2_2") (pintype "passive"))
      (node (ref "C5") (pin "2") (pinfunction "2_2") (pintype "passive"))
      (node (ref "C8") (pin "2") (pinfunction "2_2") (pintype "passive"))
      (node (ref "C9") (pin "-") (pinfunction "-_-") (pintype "passive"))
      (node (ref "CUSB") (pin "2") (pinfunction "2_2") (pintype "passive"))
      (node (ref "IC1") (pin "P$2") (pinfunction "GND_P$2") (pintype "bidirectional"))
      (node (ref "IC3") (pin "18") (pinfunction "GND_18") (pintype "power_in"))
      (node (ref "IC3") (pin "21") (pinfunction "GND_21") (pintype "power_in"))
      (node (ref "IC3") (pin "25") (pinfunction "GND_25") (pintype "power_in"))
      (node (ref "IC3") (pin "26") (pinfunction "TEST_26") (pintype "input"))
      (node (ref "IC3") (pin "7") (pinfunction "GND_7") (pintype "power_in"))
      (node (ref "IC5") (pin "2") (pinfunction "GND1_2") (pintype "bidirectional"))
      (node (ref "IC5") (pin "8") (pinfunction "GND1_8") (pintype "bidirectional"))
      (node (ref "RUSB") (pin "2") (pinfunction "2_2") (pintype "passive"))
      (node (ref "TP1") (pin "TP") (pinfunction "TP_TP") (pintype "input"))
      (node (ref "USB") (pin "P$5") (pinfunction "5_P$5") (pintype "bidirectional"))
    )
    (net (code "24") (name "IN00") (class "Default")
      (node (ref "IC12") (pin "4") (pinfunction "P$4_4") (pintype "bidirectional"))
      (node (ref "IC6") (pin "4") (pinfunction "PB0/ADC8/AREF_4") (pintype "bidirectional"))
    )
    (net (code "25") (name "Net-(C6-Pad+)") (class "Default")
      (node (ref "C6") (pin "+") (pinfunction "+_+") (pintype "passive"))
      (node (ref "R1") (pin "1") (pinfunction "1_1") (pintype "passive"))
    )
    (net (code "26") (name "Net-(IC1-VBUS)") (class "Default")
      (node (ref "C2") (pin "1") (pinfunction "1_1") (pintype "passive"))
      (node (ref "IC1") (pin "P$5") (pinfunction "VBUS_P$5") (pintype "bidirectional"))
      (node (ref "L1") (pin "2") (pinfunction "2_2") (pintype "passive"))
      (node (ref "USB") (pin "P$1") (pinfunction "1_P$1") (pintype "bidirectional"))
    )
    (net (code "27") (name "Net-(IC2-ON{slash}OFF)") (class "Default")
      (node (ref "IC2") (pin "P1") (pinfunction "ON/OFF_P1") (pintype "passive"))
      (node (ref "R2") (pin "1") (pinfunction "1_1") (pintype "passive"))
    )
    (net (code "28") (name "Net-(IC2-TRIM)") (class "Default")
      (node (ref "IC2") (pin "P5") (pinfunction "TRIM_P5") (pintype "passive"))
      (node (ref "RTRIM") (pin "2") (pinfunction "2_2") (pintype "passive"))
    )
    (net (code "29") (name "Net-(IC2-VIN)") (class "Default")
      (node (ref "C7") (pin "1") (pinfunction "1_1") (pintype "passive"))
      (node (ref "IC2") (pin "P2") (pinfunction "VIN_P2") (pintype "passive"))
      (node (ref "L2") (pin "2") (pinfunction "2_2") (pintype "passive"))
      (node (ref "R1") (pin "2") (pinfunction "2_2") (pintype "passive"))
      (node (ref "R2") (pin "2") (pinfunction "2_2") (pintype "passive"))
    )
    (net (code "30") (name "Net-(IC3-3V3OUT)") (class "Default")
      (node (ref "C10") (pin "1") (pinfunction "1_1") (pintype "passive"))
      (node (ref "IC3") (pin "17") (pinfunction "3V3OUT_17") (pintype "output"))
    )
    (net (code "31") (name "Net-(IC3-CBUS0)") (class "Default")
      (node (ref "IC3") (pin "23") (pinfunction "CBUS0_23") (pintype "bidirectional"))
      (node (ref "TX1") (pin "K") (pinfunction "K_K") (pintype "bidirectional"))
    )
    (net (code "32") (name "Net-(IC3-CBUS1)") (class "Default")
      (node (ref "IC3") (pin "22") (pinfunction "CBUS1_22") (pintype "bidirectional"))
      (node (ref "RX1") (pin "K") (pinfunction "K_K") (pintype "bidirectional"))
    )
    (net (code "33") (name "Net-(IC4-NR{slash}FB)") (class "Default")
      (node (ref "C16") (pin "2") (pinfunction "2_2") (pintype "passive"))
      (node (ref "IC4") (pin "P5") (pinfunction "NR/FB_P5") (pintype "bidirectional"))
      (node (ref "R5") (pin "1") (pinfunction "1_1") (pintype "passive"))
      (node (ref "R6") (pin "2") (pinfunction "2_2") (pintype "passive"))
    )
    (net (code "34") (name "Net-(IC6-PR1{slash}XTAL1)") (class "Default")
      (node (ref "IC6") (pin "37") (pinfunction "PR1/XTAL1_37") (pintype "bidirectional"))
      (node (ref "OSC1") (pin "P$3") (pinfunction "OUTPUT_P$3") (pintype "passive"))
    )
    (net (code "35") (name "Net-(IC8-P$4)") (class "Default")
      (node (ref "IC8") (pin "4") (pinfunction "P$4_4") (pintype "bidirectional"))
      (node (ref "R16") (pin "1") (pinfunction "1_1") (pintype "passive"))
    )
    (net (code "36") (name "Net-(IC9-P$4)") (class "Default")
      (node (ref "IC9") (pin "4") (pinfunction "P$4_4") (pintype "bidirectional"))
      (node (ref "R11") (pin "1") (pinfunction "1_1") (pintype "passive"))
    )
    (net (code "37") (name "Net-(IC10-P$4)") (class "Default")
      (node (ref "IC10") (pin "4") (pinfunction "P$4_4") (pintype "bidirectional"))
      (node (ref "R12") (pin "1") (pinfunction "1_1") (pintype "passive"))
    )
    (net (code "38") (name "Net-(IC11-P$4)") (class "Default")
      (node (ref "IC11") (pin "4") (pinfunction "P$4_4") (pintype "bidirectional"))
      (node (ref "R17") (pin "1") (pinfunction "1_1") (pintype "passive"))
    )
    (net (code "39") (name "Net-(IC13-REFCAPA)") (class "Default")
      (node (ref "C44") (pin "2") (pinfunction "2_2") (pintype "passive"))
      (node (ref "IC13") (pin "44") (pinfunction "REFCAPA_44") (pintype "bidirectional"))
      (node (ref "IC13") (pin "45") (pinfunction "REFCAPB_45") (pintype "bidirectional"))
    )
    (net (code "40") (name "Net-(IC13-REFIN{slash}REFOUT)") (class "Default")
      (node (ref "C45") (pin "2") (pinfunction "2_2") (pintype "passive"))
      (node (ref "IC13") (pin "42") (pinfunction "REFIN/REFOUT_42") (pintype "input"))
    )
    (net (code "41") (name "Net-(IC13-REGCAP0)") (class "Default")
      (node (ref "C47") (pin "2") (pinfunction "2_2") (pintype "passive"))
      (node (ref "IC13") (pin "36") (pinfunction "REGCAP0_36") (pintype "bidirectional"))
    )
    (net (code "42") (name "Net-(IC13-REGCAP1)") (class "Default")
      (node (ref "C46") (pin "2") (pinfunction "2_2") (pintype "passive"))
      (node (ref "IC13") (pin "39") (pinfunction "REGCAP1_39") (pintype "bidirectional"))
    )
    (net (code "43") (name "Net-(IC14-P$2)") (class "Default")
      (node (ref "C37") (pin "2") (pinfunction "2_2") (pintype "passive"))
      (node (ref "IC14") (pin "2") (pinfunction "P$2_2") (pintype "bidirectional"))
      (node (ref "R13") (pin "2") (pinfunction "2_2") (pintype "passive"))
    )
    (net (code "44") (name "Net-(IC14-P$4)") (class "Default")
      (node (ref "IC14") (pin "4") (pinfunction "P$4_4") (pintype "bidirectional"))
      (node (ref "R14") (pin "1") (pinfunction "1_1") (pintype "passive"))
    )
    (net (code "45") (name "Net-(IC15-P$2)") (class "Default")
      (node (ref "C39") (pin "2") (pinfunction "2_2") (pintype "passive"))
      (node (ref "IC15") (pin "2") (pinfunction "P$2_2") (pintype "bidirectional"))
      (node (ref "R14") (pin "2") (pinfunction "2_2") (pintype "passive"))
    )
    (net (code "46") (name "Net-(R3-Pad1)") (class "Default")
      (node (ref "R3") (pin "1") (pinfunction "1_1") (pintype "passive"))
      (node (ref "TX1") (pin "A") (pinfunction "A_A") (pintype "bidirectional"))
    )
    (net (code "47") (name "Net-(R4-Pad1)") (class "Default")
      (node (ref "R4") (pin "1") (pinfunction "1_1") (pintype "passive"))
      (node (ref "RX1") (pin "A") (pinfunction "A_A") (pintype "bidirectional"))
    )
    (net (code "48") (name "Net-(R15-Pad1)") (class "Default")
      (node (ref "R15") (pin "1") (pinfunction "1_1") (pintype "passive"))
      (node (ref "STATE") (pin "A") (pinfunction "A_A") (pintype "bidirectional"))
    )
    (net (code "49") (name "Net-(USB-2)") (class "Default")
      (node (ref "IC1") (pin "P$1") (pinfunction "IO1_P$1") (pintype "bidirectional"))
      (node (ref "USB") (pin "P$2") (pinfunction "2_P$2") (pintype "bidirectional"))
    )
    (net (code "50") (name "Net-(USB-3)") (class "Default")
      (node (ref "IC1") (pin "P$3") (pinfunction "IO2_P$3") (pintype "bidirectional"))
      (node (ref "USB") (pin "P$3") (pinfunction "3_P$3") (pintype "bidirectional"))
    )
    (net (code "51") (name "Net-(USB-P$1)") (class "Default")
      (node (ref "RUSB") (pin "1") (pinfunction "1_1") (pintype "passive"))
      (node (ref "USB") (pin "SHIELD_1") (pinfunction "P$1_SHIELD_1") (pintype "bidirectional"))
    )
    (net (code "52") (name "Net-(USB-P$4)") (class "Default")
      (node (ref "CUSB") (pin "1") (pinfunction "1_1") (pintype "passive"))
      (node (ref "USB") (pin "SHIELD_4") (pinfunction "P$4_SHIELD_4") (pintype "bidirectional"))
    )
    (net (code "53") (name "OS0") (class "Default")
      (node (ref "IC13") (pin "3") (pinfunction "OS0_3") (pintype "bidirectional"))
      (node (ref "IC6") (pin "22") (pinfunction "~OC0CRXD0PD2_22") (pintype "bidirectional"))
      (node (ref "R20") (pin "1") (pinfunction "1_1") (pintype "passive"))
      (node (ref "R21") (pin "2") (pinfunction "2_2") (pintype "passive"))
    )
    (net (code "54") (name "OS1") (class "Default")
      (node (ref "IC13") (pin "4") (pinfunction "OS1_4") (pintype "bidirectional"))
      (node (ref "IC6") (pin "23") (pinfunction "~OC0DTXD0PD3_23") (pintype "bidirectional"))
      (node (ref "R22") (pin "1") (pinfunction "1_1") (pintype "passive"))
      (node (ref "R23") (pin "2") (pinfunction "2_2") (pintype "passive"))
    )
    (net (code "55") (name "OS2") (class "Default")
      (node (ref "IC13") (pin "5") (pinfunction "OS2_5") (pintype "bidirectional"))
      (node (ref "IC6") (pin "24") (pinfunction "~{#SSPD4}_24") (pintype "bidirectional"))
      (node (ref "R24") (pin "1") (pinfunction "1_1") (pintype "passive"))
      (node (ref "R25") (pin "2") (pinfunction "2_2") (pintype "passive"))
    )
    (net (code "56") (name "OUT0") (class "Default")
      (node (ref "IC11") (pin "2") (pinfunction "P$2_2") (pintype "bidirectional"))
      (node (ref "IC6") (pin "40") (pinfunction "PA0/ADC0/AREF_40") (pintype "bidirectional"))
    )
    (net (code "57") (name "OUT1") (class "Default")
      (node (ref "IC10") (pin "2") (pinfunction "P$2_2") (pintype "bidirectional"))
      (node (ref "IC6") (pin "41") (pinfunction "PA1/ADC1_41") (pintype "bidirectional"))
    )
    (net (code "58") (name "OUT2") (class "Default")
      (node (ref "IC6") (pin "42") (pinfunction "PA2/ADC2_42") (pintype "bidirectional"))
      (node (ref "IC9") (pin "2") (pinfunction "P$2_2") (pintype "bidirectional"))
    )
    (net (code "59") (name "OUT3") (class "Default")
      (node (ref "IC6") (pin "43") (pinfunction "PA3/ADC3_43") (pintype "bidirectional"))
      (node (ref "IC8") (pin "2") (pinfunction "P$2_2") (pintype "bidirectional"))
    )
    (net (code "60") (name "P5.45V") (class "Default")
      (node (ref "C12") (pin "1") (pinfunction "1_1") (pintype "passive"))
      (node (ref "C13") (pin "1") (pinfunction "1_1") (pintype "passive"))
      (node (ref "C14") (pin "1") (pinfunction "1_1") (pintype "passive"))
      (node (ref "IC2") (pin "P4") (pinfunction "VOUT_P4") (pintype "passive"))
      (node (ref "IC4") (pin "P1") (pinfunction "IN_P1") (pintype "bidirectional"))
      (node (ref "IC4") (pin "P2") (pinfunction "IN_P2") (pintype "bidirectional"))
      (node (ref "IC4") (pin "P8") (pinfunction "EN_P8") (pintype "bidirectional"))
    )
    (net (code "61") (name "PDI-CLK") (class "Default")
      (node (ref "IC6") (pin "35") (pinfunction "RESET/PDI-CLK_35") (pintype "input"))
      (node (ref "PDI") (pin "5") (pinfunction "5_5") (pintype "passive"))
    )
    (net (code "62") (name "PDI-DATA") (class "Default")
      (node (ref "IC6") (pin "34") (pinfunction "PDI-DATA_34") (pintype "bidirectional"))
      (node (ref "PDI") (pin "1") (pinfunction "1_1") (pintype "passive"))
    )
    (net (code "63") (name "RANGE") (class "Default")
      (node (ref "IC13") (pin "8") (pinfunction "RANGE_8") (pintype "bidirectional"))
      (node (ref "IC6") (pin "44") (pinfunction "PA4/ADC4_44") (pintype "bidirectional"))
      (node (ref "R10") (pin "1") (pinfunction "1_1") (pintype "passive"))
      (node (ref "R9") (pin "2") (pinfunction "2_2") (pintype "passive"))
    )
    (net (code "64") (name "RESET") (class "Default")
      (node (ref "IC13") (pin "11") (pinfunction "RESET_11") (pintype "bidirectional"))
      (node (ref "IC15") (pin "4") (pinfunction "P$4_4") (pintype "bidirectional"))
      (node (ref "IC6") (pin "20") (pinfunction "~{OC0APD0}_20") (pintype "bidirectional"))
    )
    (net (code "65") (name "RTS") (class "Default")
      (node (ref "IC5") (pin "13") (pinfunction "B2_13") (pintype "bidirectional"))
      (node (ref "IC6") (pin "28") (pinfunction "~{OC0ASDAPE0}_28") (pintype "bidirectional"))
    )
    (net (code "66") (name "RXD") (class "Default")
      (node (ref "IC5") (pin "12") (pinfunction "B3_12") (pintype "bidirectional"))
      (node (ref "IC6") (pin "33") (pinfunction "~TXD0OC0DPE3_33") (pintype "bidirectional"))
    )
    (net (code "67") (name "SCK0") (class "Default")
      (node (ref "IC13") (pin "12") (pinfunction "~{RD}/SCLK_12") (pintype "bidirectional"))
      (node (ref "IC6") (pin "17") (pinfunction "PC7/SCK/TXD1/CLKO/EVO_17") (pintype "bidirectional"))
    )
    (net (code "68") (name "SDI") (class "Default")
      (node (ref "IC6") (pin "15") (pinfunction "PC5/OC1B/MOSI/XCK1_15") (pintype "bidirectional"))
    )
    (net (code "69") (name "SDO") (class "Default")
      (node (ref "IC13") (pin "24") (pinfunction "DB7/DOUTA_24") (pintype "bidirectional"))
      (node (ref "IC6") (pin "16") (pinfunction "PC6/MISO/RXD1_16") (pintype "bidirectional"))
    )
    (net (code "70") (name "STATE") (class "Default")
      (node (ref "IC6") (pin "36") (pinfunction "PR0/XTAL2_36") (pintype "bidirectional"))
      (node (ref "R15") (pin "2") (pinfunction "2_2") (pintype "passive"))
    )
    (net (code "71") (name "TXD") (class "Default")
      (node (ref "IC5") (pin "14") (pinfunction "B1_14") (pintype "bidirectional"))
      (node (ref "IC6") (pin "32") (pinfunction "~RXD0OC0CPE2_32") (pintype "bidirectional"))
    )
    (net (code "72") (name "USB5V") (class "Default")
      (node (ref "C11") (pin "1") (pinfunction "1_1") (pintype "passive"))
      (node (ref "C15") (pin "1") (pinfunction "1_1") (pintype "passive"))
      (node (ref "C8") (pin "1") (pinfunction "1_1") (pintype "passive"))
      (node (ref "C9") (pin "+") (pinfunction "+_+") (pintype "passive"))
      (node (ref "IC3") (pin "20") (pinfunction "VCC_20") (pintype "power_in"))
      (node (ref "IC3") (pin "4") (pinfunction "VCCIO_4") (pintype "power_in"))
      (node (ref "IC5") (pin "1") (pinfunction "VDD1_1") (pintype "bidirectional"))
      (node (ref "IC5") (pin "7") (pinfunction "NC/EN_7") (pintype "bidirectional"))
      (node (ref "L1") (pin "1") (pinfunction "1_1") (pintype "passive"))
      (node (ref "R3") (pin "2") (pinfunction "2_2") (pintype "passive"))
      (node (ref "R4") (pin "2") (pinfunction "2_2") (pintype "passive"))
    )
    (net (code "73") (name "USBDM") (class "Default")
      (node (ref "C5") (pin "1") (pinfunction "1_1") (pintype "passive"))
      (node (ref "IC1") (pin "P$6") (pinfunction "IO1_P$6") (pintype "bidirectional"))
      (node (ref "IC3") (pin "16") (pinfunction "USBDM_16") (pintype "bidirectional"))
    )
    (net (code "74") (name "USBDP") (class "Default")
      (node (ref "C4") (pin "1") (pinfunction "1_1") (pintype "passive"))
      (node (ref "IC1") (pin "P$4") (pinfunction "IO2_P$4") (pintype "bidirectional"))
      (node (ref "IC3") (pin "15") (pinfunction "USBDP_15") (pintype "bidirectional"))
    )
    (net (code "75") (name "VCCIO") (class "Default")
      (node (ref "C17") (pin "1") (pinfunction "1_1") (pintype "passive"))
      (node (ref "C19") (pin "1") (pinfunction "1_1") (pintype "passive"))
      (node (ref "C21") (pin "1") (pinfunction "1_1") (pintype "passive"))
      (node (ref "C22") (pin "1") (pinfunction "1_1") (pintype "passive"))
      (node (ref "C23") (pin "1") (pinfunction "1_1") (pintype "passive"))
      (node (ref "C24") (pin "1") (pinfunction "1_1") (pintype "passive"))
      (node (ref "C25") (pin "1") (pinfunction "1_1") (pintype "passive"))
      (node (ref "C26") (pin "1") (pinfunction "1_1") (pintype "passive"))
      (node (ref "C27") (pin "1") (pinfunction "1_1") (pintype "passive"))
      (node (ref "C34") (pin "1") (pinfunction "1_1") (pintype "passive"))
      (node (ref "C38") (pin "1") (pinfunction "1_1") (pintype "passive"))
      (node (ref "C40") (pin "1") (pinfunction "1_1") (pintype "passive"))
      (node (ref "CLKIN") (pin "1") (pinfunction "1_1") (pintype "passive"))
      (node (ref "IC12") (pin "5") (pinfunction "P$5_5") (pintype "bidirectional"))
      (node (ref "IC13") (pin "23") (pinfunction "VDRIVE_23") (pintype "bidirectional"))
      (node (ref "IC13") (pin "34") (pinfunction "REFSELECT_34") (pintype "bidirectional"))
      (node (ref "IC13") (pin "6") (pinfunction "~{PAR}/SER/BYTESEL_6") (pintype "bidirectional"))
      (node (ref "IC13") (pin "7") (pinfunction "~{STBY}_7") (pintype "bidirectional"))
      (node (ref "IC14") (pin "5") (pinfunction "P$5_5") (pintype "bidirectional"))
      (node (ref "IC15") (pin "5") (pinfunction "P$5_5") (pintype "bidirectional"))
      (node (ref "IC5") (pin "10") (pinfunction "NC/EN_10") (pintype "bidirectional"))
      (node (ref "IC5") (pin "16") (pinfunction "VDD2_16") (pintype "bidirectional"))
      (node (ref "IC6") (pin "19") (pinfunction "VCC_19") (pintype "power_in"))
      (node (ref "IC6") (pin "31") (pinfunction "VCC_31") (pintype "power_in"))
      (node (ref "IC6") (pin "39") (pinfunction "AVCC_39") (pintype "power_in"))
      (node (ref "IC6") (pin "9") (pinfunction "VCC_9") (pintype "power_in"))
      (node (ref "IC7") (pin "5") (pinfunction "OUT_5") (pintype "bidirectional"))
      (node (ref "OSC1") (pin "P$4") (pinfunction "VDD_P$4") (pintype "passive"))
      (node (ref "PDI") (pin "2") (pinfunction "2_2") (pintype "passive"))
      (node (ref "R10") (pin "2") (pinfunction "2_2") (pintype "passive"))
      (node (ref "R13") (pin "1") (pinfunction "1_1") (pintype "passive"))
      (node (ref "R20") (pin "2") (pinfunction "2_2") (pintype "passive"))
      (node (ref "R22") (pin "2") (pinfunction "2_2") (pintype "passive"))
      (node (ref "R24") (pin "2") (pinfunction "2_2") (pintype "passive"))
      (node (ref "R7") (pin "2") (pinfunction "2_2") (pintype "passive"))
    )
    (net (code "76") (name "unconnected-(IC3-CBUS2-Pad13)") (class "Default")
      (node (ref "IC3") (pin "13") (pinfunction "CBUS2_13") (pintype "bidirectional"))
    )
    (net (code "77") (name "unconnected-(IC3-CBUS3-Pad14)") (class "Default")
      (node (ref "IC3") (pin "14") (pinfunction "CBUS3_14") (pintype "bidirectional"))
    )
    (net (code "78") (name "unconnected-(IC3-CBUS4-Pad12)") (class "Default")
      (node (ref "IC3") (pin "12") (pinfunction "CBUS4_12") (pintype "bidirectional"))
    )
    (net (code "79") (name "unconnected-(IC3-OSCI-Pad27)") (class "Default")
      (node (ref "IC3") (pin "27") (pinfunction "OSCI_27") (pintype "input"))
    )
    (net (code "80") (name "unconnected-(IC3-OSCO-Pad28)") (class "Default")
      (node (ref "IC3") (pin "28") (pinfunction "OSCO_28") (pintype "output"))
    )
    (net (code "81") (name "unconnected-(IC3-~{DCD}-Pad10)") (class "Default")
      (node (ref "IC3") (pin "10") (pinfunction "~{DCD}_10") (pintype "input"))
    )
    (net (code "82") (name "unconnected-(IC3-~{DSR}-Pad9)") (class "Default")
      (node (ref "IC3") (pin "9") (pinfunction "~{DSR}_9") (pintype "input"))
    )
    (net (code "83") (name "unconnected-(IC3-~{DTR}-Pad2)") (class "Default")
      (node (ref "IC3") (pin "2") (pinfunction "~{DTR}_2") (pintype "output"))
    )
    (net (code "84") (name "unconnected-(IC3-~{RESET}-Pad19)") (class "Default")
      (node (ref "IC3") (pin "19") (pinfunction "~{RESET}_19") (pintype "input"))
    )
    (net (code "85") (name "unconnected-(IC3-~{RI}-Pad6)") (class "Default")
      (node (ref "IC3") (pin "6") (pinfunction "~{RI}_6") (pintype "input"))
    )
    (net (code "86") (name "unconnected-(IC6-PA5{slash}ADC5-Pad1)") (class "Default")
      (node (ref "IC6") (pin "1") (pinfunction "PA5/ADC5_1") (pintype "bidirectional"))
    )
    (net (code "87") (name "unconnected-(IC6-PA6{slash}ADC6-Pad2)") (class "Default")
      (node (ref "IC6") (pin "2") (pinfunction "PA6/ADC6_2") (pintype "bidirectional"))
    )
    (net (code "88") (name "unconnected-(IC6-PA7{slash}ADC7{slash}AC0-OUT-Pad3)") (class "Default")
      (node (ref "IC6") (pin "3") (pinfunction "PA7/ADC7/AC0-OUT_3") (pintype "bidirectional"))
    )
    (net (code "89") (name "unconnected-(IC6-PB1{slash}ADC9-Pad5)") (class "Default")
      (node (ref "IC6") (pin "5") (pinfunction "PB1/ADC9_5") (pintype "bidirectional"))
    )
    (net (code "90") (name "unconnected-(IC6-PB2{slash}ADC10{slash}DAC0-Pad6)") (class "Default")
      (node (ref "IC6") (pin "6") (pinfunction "PB2/ADC10/DAC0_6") (pintype "bidirectional"))
    )
    (net (code "91") (name "unconnected-(IC6-PB3{slash}ADC11{slash}DAC1-Pad7)") (class "Default")
      (node (ref "IC6") (pin "7") (pinfunction "PB3/ADC11/DAC1_7") (pintype "bidirectional"))
    )
    (net (code "92") (name "unconnected-(IC6-PC3{slash}OC0D{slash}TXD0-Pad13)") (class "Default")
      (node (ref "IC6") (pin "13") (pinfunction "PC3/OC0D/TXD0_13") (pintype "bidirectional"))
    )
    (net (code "93") (name "unconnected-(IC6-~RXD1MISOPD6-Pad26)") (class "Default")
      (node (ref "IC6") (pin "26") (pinfunction "~RXD1MISOPD6_26") (pintype "bidirectional"))
    )
    (net (code "94") (name "unconnected-(IC6-~XCK1MOSIPD5-Pad25)") (class "Default")
      (node (ref "IC6") (pin "25") (pinfunction "~XCK1MOSIPD5_25") (pintype "bidirectional"))
    )
    (net (code "95") (name "unconnected-(IC6-~~{TXD1SCKCLKOPD7}-Pad27)") (class "Default")
      (node (ref "IC6") (pin "27") (pinfunction "~~{TXD1SCKCLKOPD7}_27") (pintype "bidirectional"))
    )
    (net (code "96") (name "unconnected-(IC7-N{slash}C-Pad4)") (class "Default")
      (node (ref "IC7") (pin "4") (pinfunction "N/C_4") (pintype "bidirectional"))
    )
    (net (code "97") (name "unconnected-(IC13-DB8{slash}DOUTB-Pad25)") (class "Default")
      (node (ref "IC13") (pin "25") (pinfunction "DB8/DOUTB_25") (pintype "bidirectional"))
    )
    (net (code "98") (name "unconnected-(IC13-FRSTDATA-Pad15)") (class "Default")
      (node (ref "IC13") (pin "15") (pinfunction "FRSTDATA_15") (pintype "bidirectional"))
    )
    (net (code "99") (name "unconnected-(OSC1-STANDBY#-PadP$1)") (class "Default")
      (node (ref "OSC1") (pin "P$1") (pinfunction "STANDBY#_P$1") (pintype "passive"))
    )
    (net (code "100") (name "unconnected-(PDI-Pad3)") (class "Default")
      (node (ref "PDI") (pin "3") (pinfunction "3_3") (pintype "passive"))
    )
    (net (code "101") (name "unconnected-(PDI-Pad4)") (class "Default")
      (node (ref "PDI") (pin "4") (pinfunction "4_4") (pintype "passive"))
    )
    (net (code "102") (name "unconnected-(USB-4-PadP$4)") (class "Default")
      (node (ref "USB") (pin "P$4") (pinfunction "4_P$4") (pintype "bidirectional"))
    )
    (net (code "103") (name "unconnected-(USB-P$2-PadSHIELD_2)") (class "Default")
      (node (ref "USB") (pin "SHIELD_2") (pinfunction "P$2_SHIELD_2") (pintype "bidirectional"))
    )
    (net (code "104") (name "unconnected-(USB-P$3-PadSHIELD_3)") (class "Default")
      (node (ref "USB") (pin "SHIELD_3") (pinfunction "P$3_SHIELD_3") (pintype "bidirectional"))
    )
    (net (code "105") (name "~{CS_ADC}") (class "Default")
      (node (ref "IC13") (pin "13") (pinfunction "~{CS}_13") (pintype "input"))
      (node (ref "IC6") (pin "14") (pinfunction "PC4/OC1A/#SS_14") (pintype "bidirectional"))
      (node (ref "R7") (pin "1") (pinfunction "1_1") (pintype "passive"))
      (node (ref "R8") (pin "2") (pinfunction "2_2") (pintype "passive"))
    )
  )
)
